# Power.net
KiCad netlist of a schematic drawn in Altium Designer
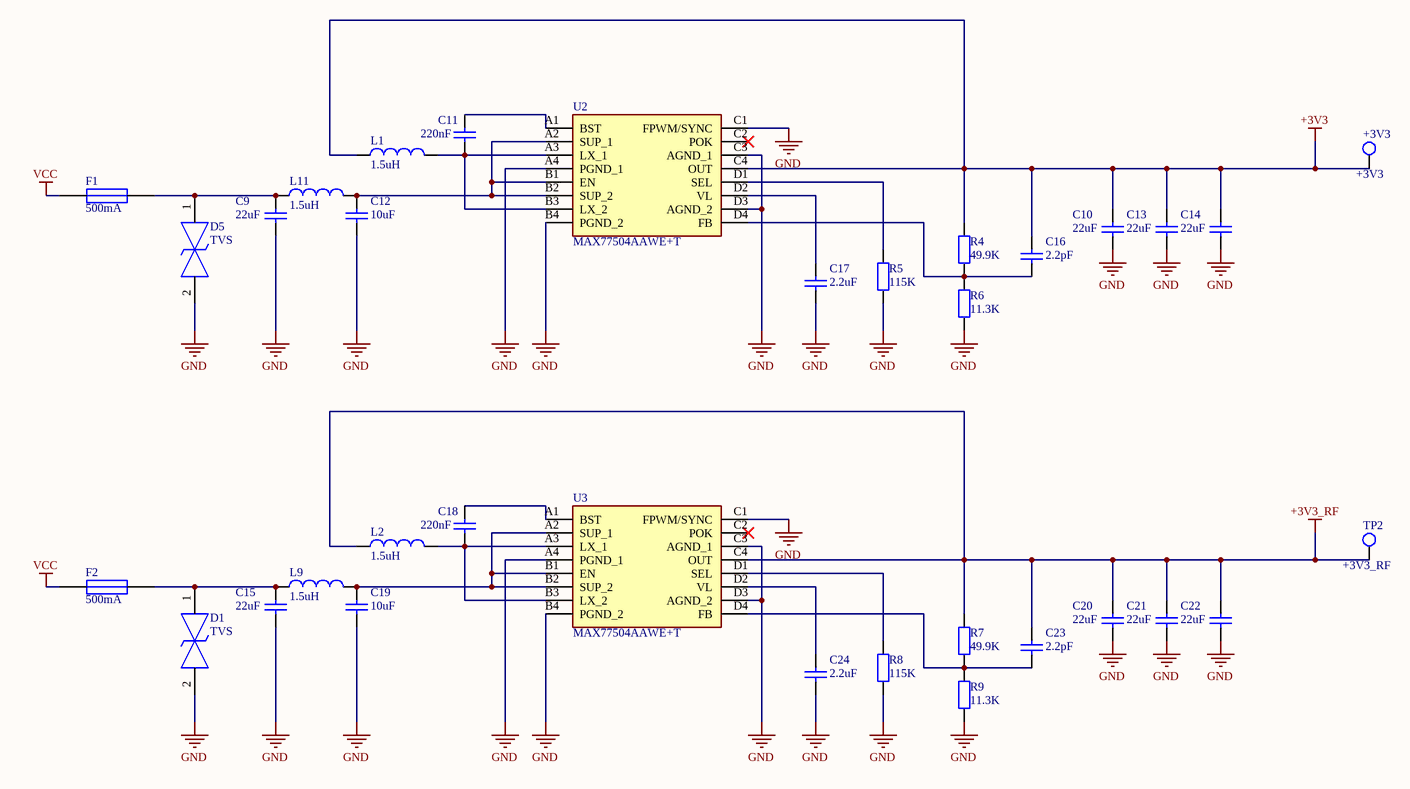
[diagram p0: Power.SchDoc]

(export (version "E")
  (design (tool "Eeschema 10.0.6"))
  (components
    (comp (ref "+3V3")
      (value "+3V3")
      (footprint "testpoint 1 mm")
      (libsource (lib "Schematic_library") (part "testpoint"))
    )
    (comp (ref "C9")
      (value "22uF")
      (footprint "SMD-0805C")
      (description "Capacitor")
      (fields (field (name "PUBLISHER") "Altium Limited"))
      (libsource (lib "Miscellaneous Devices") (part "Cap"))
    )
    (comp (ref "C10")
      (value "22uF")
      (footprint "SMD-0805C")
      (description "Capacitor")
      (fields (field (name "PUBLISHER") "Altium Limited"))
      (libsource (lib "Miscellaneous Devices") (part "Cap"))
    )
    (comp (ref "C11")
      (value "220nF")
      (footprint "SMD-0402C")
      (description "Capacitor")
      (fields (field (name "PUBLISHER") "Altium Limited"))
      (libsource (lib "Miscellaneous Devices") (part "Cap"))
    )
    (comp (ref "C12")
      (value "10uF")
      (footprint "SMD-0805C")
      (description "Capacitor")
      (fields (field (name "PUBLISHER") "Altium Limited"))
      (libsource (lib "Miscellaneous Devices") (part "Cap"))
    )
    (comp (ref "C13")
      (value "22uF")
      (footprint "SMD-0805C")
      (description "Capacitor")
      (fields (field (name "PUBLISHER") "Altium Limited"))
      (libsource (lib "Miscellaneous Devices") (part "Cap"))
    )
    (comp (ref "C14")
      (value "22uF")
      (footprint "SMD-0805C")
      (description "Capacitor")
      (fields (field (name "PUBLISHER") "Altium Limited"))
      (libsource (lib "Miscellaneous Devices") (part "Cap"))
    )
    (comp (ref "C15")
      (value "22uF")
      (footprint "SMD-0805C")
      (description "Capacitor")
      (fields (field (name "PUBLISHER") "Altium Limited"))
      (libsource (lib "Miscellaneous Devices") (part "Cap"))
    )
    (comp (ref "C16")
      (value "2.2pF")
      (footprint "SMD-0402C")
      (description "Capacitor")
      (fields (field (name "PUBLISHER") "Altium Limited"))
      (libsource (lib "Miscellaneous Devices") (part "Cap"))
    )
    (comp (ref "C17")
      (value "2.2uF")
      (footprint "SMD-0402C")
      (description "Capacitor")
      (fields (field (name "PUBLISHER") "Altium Limited"))
      (libsource (lib "Miscellaneous Devices") (part "Cap"))
    )
    (comp (ref "C18")
      (value "220nF")
      (footprint "SMD-0402C")
      (description "Capacitor")
      (fields (field (name "PUBLISHER") "Altium Limited"))
      (libsource (lib "Miscellaneous Devices") (part "Cap"))
    )
    (comp (ref "C19")
      (value "10uF")
      (footprint "SMD-0805C")
      (description "Capacitor")
      (fields (field (name "PUBLISHER") "Altium Limited"))
      (libsource (lib "Miscellaneous Devices") (part "Cap"))
    )
    (comp (ref "C20")
      (value "22uF")
      (footprint "SMD-0805C")
      (description "Capacitor")
      (fields (field (name "PUBLISHER") "Altium Limited"))
      (libsource (lib "Miscellaneous Devices") (part "Cap"))
    )
    (comp (ref "C21")
      (value "22uF")
      (footprint "SMD-0805C")
      (description "Capacitor")
      (fields (field (name "PUBLISHER") "Altium Limited"))
      (libsource (lib "Miscellaneous Devices") (part "Cap"))
    )
    (comp (ref "C22")
      (value "22uF")
      (footprint "SMD-0805C")
      (description "Capacitor")
      (fields (field (name "PUBLISHER") "Altium Limited"))
      (libsource (lib "Miscellaneous Devices") (part "Cap"))
    )
    (comp (ref "C23")
      (value "2.2pF")
      (footprint "SMD-0402C")
      (description "Capacitor")
      (fields (field (name "PUBLISHER") "Altium Limited"))
      (libsource (lib "Miscellaneous Devices") (part "Cap"))
    )
    (comp (ref "C24")
      (value "2.2uF")
      (footprint "SMD-0402C")
      (description "Capacitor")
      (fields (field (name "PUBLISHER") "Altium Limited"))
      (libsource (lib "Miscellaneous Devices") (part "Cap"))
    )
    (comp (ref "D1")
      (value "TVS")
      (footprint "TPD1E10B09DPYR")
      (fields
        (field (name "MOUSER PART NUMBER") "595-TPD1E10B09DPYR")
        (field (name "MANUFACTURER_PART_NUMBER") "TPD1E10B09DPYR")
      )
      (libsource (lib "Schematic_library") (part "TPD1E10B09DPYR"))
    )
    (comp (ref "D5")
      (value "TVS")
      (footprint "TPD1E10B09DPYR")
      (fields
        (field (name "MOUSER PART NUMBER") "595-TPD1E10B09DPYR")
        (field (name "MANUFACTURER_PART_NUMBER") "TPD1E10B09DPYR")
      )
      (libsource (lib "Schematic_library") (part "TPD1E10B09DPYR"))
    )
    (comp (ref "F1")
      (value "500mA")
      (footprint "SMD-1206-RES")
      (description "JB12S5000R\r\nSurface Mount Fuses JB12S SMD Fuse 63V 0.5A Slow 1206 3.2mm X 1.6mm")
      (fields
        (field (name "MOUSER PART NUMBER") "652-SF-1206S050-2")
        (field (name "MANUFACTURER_PART_NUMBER") "SF-1206S050-2")
      )
      (libsource (lib "Schematic_library") (part "Fuse"))
    )
    (comp (ref "F2")
      (value "500mA")
      (footprint "SMD-1206-RES")
      (description "JB12S5000R\r\nSurface Mount Fuses JB12S SMD Fuse 63V 0.5A Slow 1206 3.2mm X 1.6mm")
      (fields
        (field (name "MOUSER PART NUMBER") "652-SF-1206S050-2")
        (field (name "MANUFACTURER_PART_NUMBER") "SF-1206S050-2")
      )
      (libsource (lib "Schematic_library") (part "Fuse"))
    )
    (comp (ref "L1")
      (value "1.5uH")
      (footprint "SMD-0603-RES")
      (description "Inductor")
      (fields (field (name "PUBLISHER") "Altium Limited"))
      (libsource (lib "Miscellaneous Devices") (part "Inductor"))
    )
    (comp (ref "L2")
      (value "1.5uH")
      (footprint "SMD-0603-RES")
      (description "Inductor")
      (fields (field (name "PUBLISHER") "Altium Limited"))
      (libsource (lib "Miscellaneous Devices") (part "Inductor"))
    )
    (comp (ref "L9")
      (value "1.5uH")
      (footprint "SMD-0603-RES")
      (description "Inductor")
      (fields (field (name "PUBLISHER") "Altium Limited"))
      (libsource (lib "Miscellaneous Devices") (part "Inductor"))
    )
    (comp (ref "L11")
      (value "1.5uH")
      (footprint "SMD-0603-RES")
      (description "Inductor")
      (fields (field (name "PUBLISHER") "Altium Limited"))
      (libsource (lib "Miscellaneous Devices") (part "Inductor"))
    )
    (comp (ref "R4")
      (value "49.9K")
      (footprint "SMD-0402-RES")
      (description "Resistor")
      (fields (field (name "PUBLISHER") "Altium Limited"))
      (libsource (lib "Miscellaneous Devices") (part "Res2"))
    )
    (comp (ref "R5")
      (value "115K")
      (footprint "SMD-0402-RES")
      (description "Resistor")
      (fields (field (name "PUBLISHER") "Altium Limited"))
      (libsource (lib "Miscellaneous Devices") (part "Res2"))
    )
    (comp (ref "R6")
      (value "11.3K")
      (footprint "SMD-0402-RES")
      (description "Resistor")
      (fields (field (name "PUBLISHER") "Altium Limited"))
      (libsource (lib "Miscellaneous Devices") (part "Res2"))
    )
    (comp (ref "R7")
      (value "49.9K")
      (footprint "SMD-0402-RES")
      (description "Resistor")
      (fields (field (name "PUBLISHER") "Altium Limited"))
      (libsource (lib "Miscellaneous Devices") (part "Res2"))
    )
    (comp (ref "R8")
      (value "115K")
      (footprint "SMD-0402-RES")
      (description "Resistor")
      (fields (field (name "PUBLISHER") "Altium Limited"))
      (libsource (lib "Miscellaneous Devices") (part "Res2"))
    )
    (comp (ref "R9")
      (value "11.3K")
      (footprint "SMD-0402-RES")
      (description "Resistor")
      (fields (field (name "PUBLISHER") "Altium Limited"))
      (libsource (lib "Miscellaneous Devices") (part "Res2"))
    )
    (comp (ref "TP2")
      (value "+3V3_RF")
      (footprint "testpoint 1 mm")
      (libsource (lib "Schematic_library") (part "testpoint"))
    )
    (comp (ref "U2")
      (value "MAX77504AAWE+T")
      (footprint "MAX77504AAWE+T")
      (description "Switching Voltage Regulators High-Efficiency Buck")
      (fields (field (name "MOUSER PART NUMBER") "700-MAX77504AAWE+T"))
      (libsource (lib "Schematic_library") (part "MAX77504AAWE+T"))
    )
    (comp (ref "U3")
      (value "MAX77504AAWE+T")
      (footprint "MAX77504AAWE+T")
      (description "Switching Voltage Regulators High-Efficiency Buck")
      (fields (field (name "MOUSER PART NUMBER") "700-MAX77504AAWE+T"))
      (libsource (lib "Schematic_library") (part "MAX77504AAWE+T"))
    )
  )
  (nets
    (net (code "1") (name "+3V3") (class "Default")
      (node (ref "+3V3") (pin "1") (pinfunction "1_1") (pintype "passive"))
      (node (ref "C10") (pin "2") (pinfunction "2_2") (pintype "passive"))
      (node (ref "C13") (pin "2") (pinfunction "2_2") (pintype "passive"))
      (node (ref "C14") (pin "2") (pinfunction "2_2") (pintype "passive"))
      (node (ref "C16") (pin "2") (pinfunction "2_2") (pintype "passive"))
      (node (ref "L1") (pin "1") (pinfunction "1_1") (pintype "passive"))
      (node (ref "R4") (pin "2") (pinfunction "2_2") (pintype "passive"))
      (node (ref "U2") (pin "C4") (pinfunction "OUT_C4") (pintype "passive"))
    )
    (net (code "2") (name "+3V3_RF") (class "Default")
      (node (ref "C20") (pin "2") (pinfunction "2_2") (pintype "passive"))
      (node (ref "C21") (pin "2") (pinfunction "2_2") (pintype "passive"))
      (node (ref "C22") (pin "2") (pinfunction "2_2") (pintype "passive"))
      (node (ref "C23") (pin "2") (pinfunction "2_2") (pintype "passive"))
      (node (ref "L2") (pin "1") (pinfunction "1_1") (pintype "passive"))
      (node (ref "R7") (pin "2") (pinfunction "2_2") (pintype "passive"))
      (node (ref "TP2") (pin "1") (pinfunction "1_1") (pintype "passive"))
      (node (ref "U3") (pin "C4") (pinfunction "OUT_C4") (pintype "passive"))
    )
    (net (code "3") (name "GND") (class "Default")
      (node (ref "C10") (pin "1") (pinfunction "1_1") (pintype "passive"))
      (node (ref "C12") (pin "1") (pinfunction "1_1") (pintype "passive"))
      (node (ref "C13") (pin "1") (pinfunction "1_1") (pintype "passive"))
      (node (ref "C14") (pin "1") (pinfunction "1_1") (pintype "passive"))
      (node (ref "C15") (pin "1") (pinfunction "1_1") (pintype "passive"))
      (node (ref "C17") (pin "1") (pinfunction "1_1") (pintype "passive"))
      (node (ref "C19") (pin "1") (pinfunction "1_1") (pintype "passive"))
      (node (ref "C20") (pin "1") (pinfunction "1_1") (pintype "passive"))
      (node (ref "C21") (pin "1") (pinfunction "1_1") (pintype "passive"))
      (node (ref "C22") (pin "1") (pinfunction "1_1") (pintype "passive"))
      (node (ref "C24") (pin "1") (pinfunction "1_1") (pintype "passive"))
      (node (ref "C9") (pin "1") (pinfunction "1_1") (pintype "passive"))
      (node (ref "D1") (pin "2") (pinfunction "2_2") (pintype "passive"))
      (node (ref "D5") (pin "2") (pinfunction "2_2") (pintype "passive"))
      (node (ref "R5") (pin "1") (pinfunction "1_1") (pintype "passive"))
      (node (ref "R6") (pin "1") (pinfunction "1_1") (pintype "passive"))
      (node (ref "R8") (pin "1") (pinfunction "1_1") (pintype "passive"))
      (node (ref "R9") (pin "1") (pinfunction "1_1") (pintype "passive"))
      (node (ref "U2") (pin "A4") (pinfunction "PGND_1_A4") (pintype "passive"))
      (node (ref "U2") (pin "B4") (pinfunction "PGND_2_B4") (pintype "passive"))
      (node (ref "U2") (pin "C1") (pinfunction "FPWM/SYNC_C1") (pintype "passive"))
      (node (ref "U2") (pin "C3") (pinfunction "AGND_1_C3") (pintype "passive"))
      (node (ref "U2") (pin "D3") (pinfunction "AGND_2_D3") (pintype "passive"))
      (node (ref "U3") (pin "A4") (pinfunction "PGND_1_A4") (pintype "passive"))
      (node (ref "U3") (pin "B4") (pinfunction "PGND_2_B4") (pintype "passive"))
      (node (ref "U3") (pin "C1") (pinfunction "FPWM/SYNC_C1") (pintype "passive"))
      (node (ref "U3") (pin "C3") (pinfunction "AGND_1_C3") (pintype "passive"))
      (node (ref "U3") (pin "D3") (pinfunction "AGND_2_D3") (pintype "passive"))
    )
    (net (code "4") (name "Net-(C9-Pad2)") (class "Default")
      (node (ref "C9") (pin "2") (pinfunction "2_2") (pintype "passive"))
      (node (ref "D5") (pin "1") (pinfunction "1_1") (pintype "passive"))
      (node (ref "F1") (pin "2") (pinfunction "2_2") (pintype "passive"))
      (node (ref "L11") (pin "1") (pinfunction "1_1") (pintype "passive"))
    )
    (net (code "5") (name "Net-(C15-Pad2)") (class "Default")
      (node (ref "C15") (pin "2") (pinfunction "2_2") (pintype "passive"))
      (node (ref "D1") (pin "1") (pinfunction "1_1") (pintype "passive"))
      (node (ref "F2") (pin "2") (pinfunction "2_2") (pintype "passive"))
      (node (ref "L9") (pin "1") (pinfunction "1_1") (pintype "passive"))
    )
    (net (code "6") (name "Net-(U2-BST)") (class "Default")
      (node (ref "C11") (pin "2") (pinfunction "2_2") (pintype "passive"))
      (node (ref "U2") (pin "A1") (pinfunction "BST_A1") (pintype "passive"))
    )
    (net (code "7") (name "Net-(U2-EN)") (class "Default")
      (node (ref "C12") (pin "2") (pinfunction "2_2") (pintype "passive"))
      (node (ref "L11") (pin "2") (pinfunction "2_2") (pintype "passive"))
      (node (ref "U2") (pin "A2") (pinfunction "SUP_1_A2") (pintype "passive"))
      (node (ref "U2") (pin "B1") (pinfunction "EN_B1") (pintype "passive"))
      (node (ref "U2") (pin "B2") (pinfunction "SUP_2_B2") (pintype "passive"))
    )
    (net (code "8") (name "Net-(U2-FB)") (class "Default")
      (node (ref "C16") (pin "1") (pinfunction "1_1") (pintype "passive"))
      (node (ref "R4") (pin "1") (pinfunction "1_1") (pintype "passive"))
      (node (ref "R6") (pin "2") (pinfunction "2_2") (pintype "passive"))
      (node (ref "U2") (pin "D4") (pinfunction "FB_D4") (pintype "passive"))
    )
    (net (code "9") (name "Net-(U2-LX_1)") (class "Default")
      (node (ref "C11") (pin "1") (pinfunction "1_1") (pintype "passive"))
      (node (ref "L1") (pin "2") (pinfunction "2_2") (pintype "passive"))
      (node (ref "U2") (pin "A3") (pinfunction "LX_1_A3") (pintype "passive"))
      (node (ref "U2") (pin "B3") (pinfunction "LX_2_B3") (pintype "passive"))
    )
    (net (code "10") (name "Net-(U2-SEL)") (class "Default")
      (node (ref "R5") (pin "2") (pinfunction "2_2") (pintype "passive"))
      (node (ref "U2") (pin "D1") (pinfunction "SEL_D1") (pintype "passive"))
    )
    (net (code "11") (name "Net-(U2-VL)") (class "Default")
      (node (ref "C17") (pin "2") (pinfunction "2_2") (pintype "passive"))
      (node (ref "U2") (pin "D2") (pinfunction "VL_D2") (pintype "passive"))
    )
    (net (code "12") (name "Net-(U3-BST)") (class "Default")
      (node (ref "C18") (pin "2") (pinfunction "2_2") (pintype "passive"))
      (node (ref "U3") (pin "A1") (pinfunction "BST_A1") (pintype "passive"))
    )
    (net (code "13") (name "Net-(U3-EN)") (class "Default")
      (node (ref "C19") (pin "2") (pinfunction "2_2") (pintype "passive"))
      (node (ref "L9") (pin "2") (pinfunction "2_2") (pintype "passive"))
      (node (ref "U3") (pin "A2") (pinfunction "SUP_1_A2") (pintype "passive"))
      (node (ref "U3") (pin "B1") (pinfunction "EN_B1") (pintype "passive"))
      (node (ref "U3") (pin "B2") (pinfunction "SUP_2_B2") (pintype "passive"))
    )
    (net (code "14") (name "Net-(U3-FB)") (class "Default")
      (node (ref "C23") (pin "1") (pinfunction "1_1") (pintype "passive"))
      (node (ref "R7") (pin "1") (pinfunction "1_1") (pintype "passive"))
      (node (ref "R9") (pin "2") (pinfunction "2_2") (pintype "passive"))
      (node (ref "U3") (pin "D4") (pinfunction "FB_D4") (pintype "passive"))
    )
    (net (code "15") (name "Net-(U3-LX_1)") (class "Default")
      (node (ref "C18") (pin "1") (pinfunction "1_1") (pintype "passive"))
      (node (ref "L2") (pin "2") (pinfunction "2_2") (pintype "passive"))
      (node (ref "U3") (pin "A3") (pinfunction "LX_1_A3") (pintype "passive"))
      (node (ref "U3") (pin "B3") (pinfunction "LX_2_B3") (pintype "passive"))
    )
    (net (code "16") (name "Net-(U3-SEL)") (class "Default")
      (node (ref "R8") (pin "2") (pinfunction "2_2") (pintype "passive"))
      (node (ref "U3") (pin "D1") (pinfunction "SEL_D1") (pintype "passive"))
    )
    (net (code "17") (name "Net-(U3-VL)") (class "Default")
      (node (ref "C24") (pin "2") (pinfunction "2_2") (pintype "passive"))
      (node (ref "U3") (pin "D2") (pinfunction "VL_D2") (pintype "passive"))
    )
    (net (code "18") (name "VCC") (class "Default")
      (node (ref "F1") (pin "1") (pinfunction "1_1") (pintype "passive"))
      (node (ref "F2") (pin "1") (pinfunction "1_1") (pintype "passive"))
    )
    (net (code "19") (name "unconnected-(U2-POK-PadC2)") (class "Default")
      (node (ref "U2") (pin "C2") (pinfunction "POK_C2") (pintype "passive+no_connect"))
    )
    (net (code "20") (name "unconnected-(U3-POK-PadC2)") (class "Default")
      (node (ref "U3") (pin "C2") (pinfunction "POK_C2") (pintype "passive+no_connect"))
    )
  )
)
